# STM32.net
KiCad netlist of a schematic drawn in Altium Designer
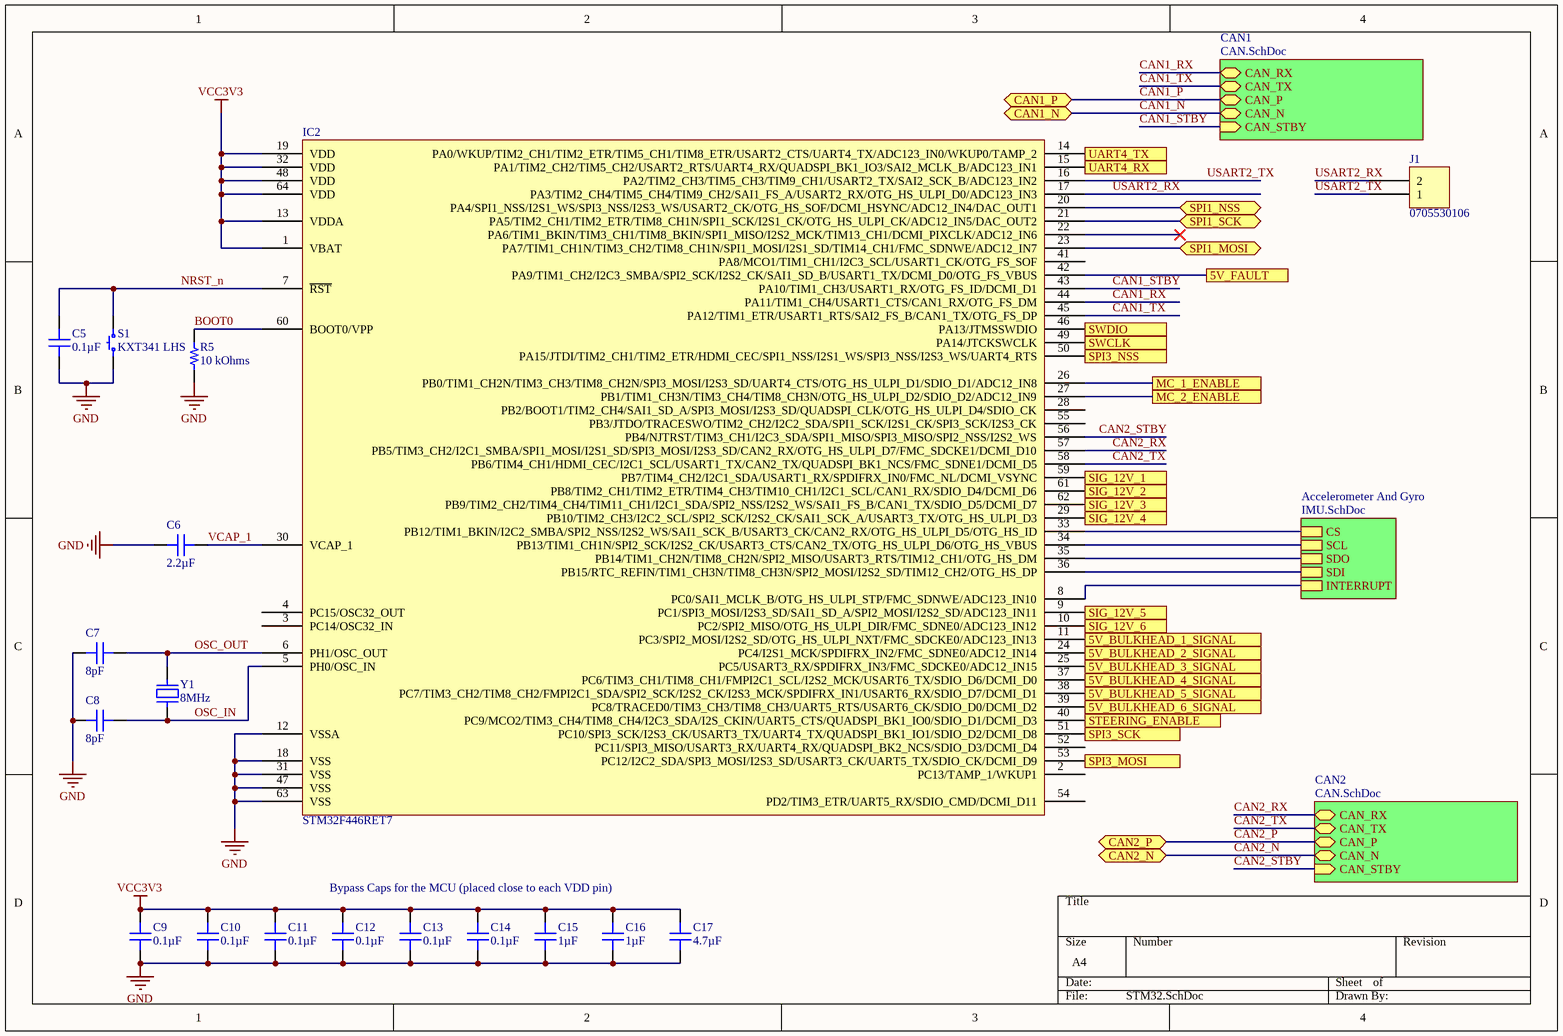
[diagram p0: STM32.SchDoc]

(export (version "E")
  (design (tool "Eeschema 10.0.6"))
  (components
    (comp (ref "C5")
      (value "0.1µF")
      (footprint "CAP 0402_1005")
      (description "CAP CER 0402 0.1UF 16V X7R 10%")
      (fields (field (name "PART NUMBER") "C0402C104K4RECAUTO") (field (name "MANUFACTURER") "KEMET"))
      (libsource (lib "CAL") (part "Capacitor"))
    )
    (comp (ref "C6")
      (value "2.2µF")
      (footprint "CAP 0402_1005")
      (description "CAP CER 2.2UF 16V X5R 0402")
      (fields
        (field (name "PART NUMBER") "CL05A225KO5NQNC")
        (field (name "MANUFACTURER") "Samsung Electro-Mechanics")
      )
      (libsource (lib "CAL") (part "Capacitor"))
    )
    (comp (ref "C7")
      (value "8pF")
      (footprint "CAP 0402_1005")
      (description "CAP CER 8PF 50V NP0 0402")
      (fields
        (field (name "PART NUMBER") "C1005NP01H080D050BA")
        (field (name "MANUFACTURER") "TDK Corporation")
      )
      (libsource (lib "Celestial") (part "Capacitor"))
    )
    (comp (ref "C8")
      (value "8pF")
      (footprint "CAP 0402_1005")
      (description "CAP CER 8PF 50V NP0 0402")
      (fields
        (field (name "PART NUMBER") "C1005NP01H080D050BA")
        (field (name "MANUFACTURER") "TDK Corporation")
      )
      (libsource (lib "Celestial") (part "Capacitor"))
    )
    (comp (ref "C9")
      (value "0.1µF")
      (footprint "CAP 0402_1005")
      (description "CAP CER 0402 0.1UF 16V X7R 10%")
      (fields (field (name "PART NUMBER") "C0402C104K4RECAUTO") (field (name "MANUFACTURER") "KEMET"))
      (libsource (lib "CAL") (part "Capacitor"))
    )
    (comp (ref "C10")
      (value "0.1µF")
      (footprint "CAP 0402_1005")
      (description "CAP CER 0402 0.1UF 16V X7R 10%")
      (fields (field (name "PART NUMBER") "C0402C104K4RECAUTO") (field (name "MANUFACTURER") "KEMET"))
      (libsource (lib "CAL") (part "Capacitor"))
    )
    (comp (ref "C11")
      (value "0.1µF")
      (footprint "CAP 0402_1005")
      (description "CAP CER 0402 0.1UF 16V X7R 10%")
      (fields (field (name "PART NUMBER") "C0402C104K4RECAUTO") (field (name "MANUFACTURER") "KEMET"))
      (libsource (lib "CAL") (part "Capacitor"))
    )
    (comp (ref "C12")
      (value "0.1µF")
      (footprint "CAP 0402_1005")
      (description "CAP CER 0402 0.1UF 16V X7R 10%")
      (fields (field (name "PART NUMBER") "C0402C104K4RECAUTO") (field (name "MANUFACTURER") "KEMET"))
      (libsource (lib "CAL") (part "Capacitor"))
    )
    (comp (ref "C13")
      (value "0.1µF")
      (footprint "CAP 0402_1005")
      (description "CAP CER 0402 0.1UF 16V X7R 10%")
      (fields (field (name "PART NUMBER") "C0402C104K4RECAUTO") (field (name "MANUFACTURER") "KEMET"))
      (libsource (lib "CAL") (part "Capacitor"))
    )
    (comp (ref "C14")
      (value "0.1µF")
      (footprint "CAP 0402_1005")
      (description "CAP CER 0402 0.1UF 16V X7R 10%")
      (fields (field (name "PART NUMBER") "C0402C104K4RECAUTO") (field (name "MANUFACTURER") "KEMET"))
      (libsource (lib "CAL") (part "Capacitor"))
    )
    (comp (ref "C15")
      (value "1µF")
      (footprint "CAP 0402_1005")
      (description "CAP CER 1UF 10V X5R 0402")
      (fields
        (field (name "PART NUMBER") "CGB2A1X5R1A105K033BC")
        (field (name "MANUFACTURER") "TDK Corporation")
      )
      (libsource (lib "CAL") (part "Capacitor"))
    )
    (comp (ref "C16")
      (value "1µF")
      (footprint "CAP 0402_1005")
      (description "CAP CER 1UF 10V X5R 0402")
      (fields
        (field (name "PART NUMBER") "CGB2A1X5R1A105K033BC")
        (field (name "MANUFACTURER") "TDK Corporation")
      )
      (libsource (lib "CAL") (part "Capacitor"))
    )
    (comp (ref "C17")
      (value "4.7µF")
      (footprint "CAP 0402_1005")
      (description "CAP CER 4.7UF 10V X5R 0402")
      (fields
        (field (name "PART NUMBER") "C1005X5R1A475K050BC")
        (field (name "MANUFACTURER") "TDK Corporation")
      )
      (libsource (lib "CAL") (part "Capacitor"))
    )
    (comp (ref "IC2")
      (value "STM32F446RET7")
      (footprint "ST LQFP-64 10X10MM")
      (description "IC MCU 32BIT 512KB FLASH 64LQFP")
      (fields (field (name "MANUFACTURER") "STMicroelectronics"))
      (libsource (lib "Celestial") (part "ST STM32F446 64PIN"))
    )
    (comp (ref "J1")
      (value "0705530106")
      (footprint "MOLEX SDA-70553-2PIN")
      (description "CONN HEADER R/A 2POS 2.54MM")
      (fields (field (name "MANUFACTURER") "Molex"))
      (libsource (lib "Celestial") (part "2 Pin"))
    )
    (comp (ref "R5")
      (value "10 kOhms")
      (footprint "RES 0402_1005")
      (description "RES SMD 10K OHM 0.5% 1/16W 0402")
      (fields (field (name "PART NUMBER") "CRCW040210K0DHEDP") (field (name "MANUFACTURER") "Vishay Dale"))
      (libsource (lib "CAL") (part "Resistor"))
    )
    (comp (ref "S1")
      (value "KXT341 LHS")
      (footprint "C&K KXT3")
      (description "SWITCH TACTILE SPST-NO 0.02A 15V")
      (fields (field (name "MANUFACTURER") "C&K"))
      (libsource (lib "Celestial") (part "SPST-NO 2 PIN"))
    )
    (comp (ref "Y1")
      (value "8MHz")
      (footprint "NDK NX3225GD")
      (description "CRYSTAL 8.0000MHZ 8PF SMD")
      (fields
        (field (name "PART NUMBER") "NX3225GD-8MHZ-STD-CRA-3")
        (field (name "MANUFACTURER") "NDK America, Inc.")
      )
      (libsource (lib "Celestial") (part "NDK NX3225GD"))
    )
  )
  (nets
    (net (code "1") (name "/5V_BULKHEAD_1_SIGNAL") (class "Default")
      (node (ref "IC2") (pin "11") (pinfunction "PC3/SPI2_MOSI/I2S2_SD/OTG_HS_ULPI_NXT/FMC_SDCKE0/ADC123_IN13_11") (pintype "passive"))
    )
    (net (code "2") (name "/5V_BULKHEAD_2_SIGNAL") (class "Default")
      (node (ref "IC2") (pin "24") (pinfunction "PC4/I2S1_MCK/SPDIFRX_IN2/FMC_SDNE0/ADC12_IN14_24") (pintype "passive"))
    )
    (net (code "3") (name "/5V_BULKHEAD_3_SIGNAL") (class "Default")
      (node (ref "IC2") (pin "25") (pinfunction "PC5/USART3_RX/SPDIFRX_IN3/FMC_SDCKE0/ADC12_IN15_25") (pintype "passive"))
    )
    (net (code "4") (name "/5V_BULKHEAD_4_SIGNAL") (class "Default")
      (node (ref "IC2") (pin "37") (pinfunction "PC6/TIM3_CH1/TIM8_CH1/FMPI2C1_SCL/I2S2_MCK/USART6_TX/SDIO_D6/DCMI_D0_37") (pintype "passive"))
    )
    (net (code "5") (name "/5V_BULKHEAD_5_SIGNAL") (class "Default")
      (node (ref "IC2") (pin "38") (pinfunction "PC7/TIM3_CH2/TIM8_CH2/FMPI2C1_SDA/SPI2_SCK/I2S2_CK/I2S3_MCK/SPDIFRX_IN1/USART6_RX/SDIO_D7/DCMI_D1_38") (pintype "passive"))
    )
    (net (code "6") (name "/5V_BULKHEAD_6_SIGNAL") (class "Default")
      (node (ref "IC2") (pin "39") (pinfunction "PC8/TRACED0/TIM3_CH3/TIM8_CH3/UART5_RTS/USART6_CK/SDIO_D0/DCMI_D2_39") (pintype "passive"))
    )
    (net (code "7") (name "/5V_FAULT") (class "Default")
      (node (ref "IC2") (pin "42") (pinfunction "PA9/TIM1_CH2/I2C3_SMBA/SPI2_SCK/I2S2_CK/SAI1_SD_B/USART1_TX/DCMI_D0/OTG_FS_VBUS_42") (pintype "passive"))
    )
    (net (code "8") (name "/BOOT0") (class "Default")
      (node (ref "IC2") (pin "60") (pinfunction "BOOT0/VPP_60") (pintype "passive"))
      (node (ref "R5") (pin "2") (pinfunction "2_2") (pintype "passive"))
    )
    (net (code "11") (name "/CAN1_RX") (class "Default")
      (node (ref "IC2") (pin "44") (pinfunction "PA11/TIM1_CH4/USART1_CTS/CAN1_RX/OTG_FS_DM_44") (pintype "passive"))
    )
    (net (code "12") (name "/CAN1_STBY") (class "Default")
      (node (ref "IC2") (pin "43") (pinfunction "PA10/TIM1_CH3/USART1_RX/OTG_FS_ID/DCMI_D1_43") (pintype "passive"))
    )
    (net (code "13") (name "/CAN1_TX") (class "Default")
      (node (ref "IC2") (pin "45") (pinfunction "PA12/TIM1_ETR/USART1_RTS/SAI2_FS_B/CAN1_TX/OTG_FS_DP_45") (pintype "passive"))
    )
    (net (code "16") (name "/CAN2_RX") (class "Default")
      (node (ref "IC2") (pin "57") (pinfunction "PB5/TIM3_CH2/I2C1_SMBA/SPI1_MOSI/I2S1_SD/SPI3_MOSI/I2S3_SD/CAN2_RX/OTG_HS_ULPI_D7/FMC_SDCKE1/DCMI_D10_57") (pintype "passive"))
    )
    (net (code "17") (name "/CAN2_STBY") (class "Default")
      (node (ref "IC2") (pin "56") (pinfunction "PB4/NJTRST/TIM3_CH1/I2C3_SDA/SPI1_MISO/SPI3_MISO/SPI2_NSS/I2S2_WS_56") (pintype "passive"))
    )
    (net (code "18") (name "/CAN2_TX") (class "Default")
      (node (ref "IC2") (pin "58") (pinfunction "PB6/TIM4_CH1/HDMI_CEC/I2C1_SCL/USART1_TX/CAN2_TX/QUADSPI_BK1_NCS/FMC_SDNE1/DCMI_D5_58") (pintype "passive"))
    )
    (net (code "19") (name "/CS") (class "Default")
      (node (ref "IC2") (pin "33") (pinfunction "PB12/TIM1_BKIN/I2C2_SMBA/SPI2_NSS/I2S2_WS/SAI1_SCK_B/USART3_CK/CAN2_RX/OTG_HS_ULPI_D5/OTG_HS_ID_33") (pintype "passive"))
    )
    (net (code "20") (name "/INTERRUPT") (class "Default")
      (node (ref "IC2") (pin "8") (pinfunction "PC0/SAI1_MCLK_B/OTG_HS_ULPI_STP/FMC_SDNWE/ADC123_IN10_8") (pintype "passive"))
    )
    (net (code "21") (name "/MC_1_ENABLE") (class "Default")
      (node (ref "IC2") (pin "26") (pinfunction "PB0/TIM1_CH2N/TIM3_CH3/TIM8_CH2N/SPI3_MOSI/I2S3_SD/UART4_CTS/OTG_HS_ULPI_D1/SDIO_D1/ADC12_IN8_26") (pintype "passive"))
    )
    (net (code "22") (name "/MC_2_ENABLE") (class "Default")
      (node (ref "IC2") (pin "27") (pinfunction "PB1/TIM1_CH3N/TIM3_CH4/TIM8_CH3N/OTG_HS_ULPI_D2/SDIO_D2/ADC12_IN9_27") (pintype "passive"))
    )
    (net (code "23") (name "/NRST_n") (class "Default")
      (node (ref "C5") (pin "2") (pinfunction "2_2") (pintype "passive"))
      (node (ref "IC2") (pin "7") (pinfunction "~{RST}_7") (pintype "passive"))
      (node (ref "S1") (pin "2") (pinfunction "2_2") (pintype "passive"))
    )
    (net (code "24") (name "/OSC_IN") (class "Default")
      (node (ref "C8") (pin "2") (pinfunction "2_2") (pintype "passive"))
      (node (ref "IC2") (pin "5") (pinfunction "PH0/OSC_IN_5") (pintype "passive"))
      (node (ref "Y1") (pin "1") (pinfunction "1_1") (pintype "passive"))
    )
    (net (code "25") (name "/OSC_OUT") (class "Default")
      (node (ref "C7") (pin "2") (pinfunction "2_2") (pintype "passive"))
      (node (ref "IC2") (pin "6") (pinfunction "PH1/OSC_OUT_6") (pintype "passive"))
      (node (ref "Y1") (pin "2") (pinfunction "2_2") (pintype "passive"))
    )
    (net (code "26") (name "/SCL") (class "Default")
      (node (ref "IC2") (pin "34") (pinfunction "PB13/TIM1_CH1N/SPI2_SCK/I2S2_CK/USART3_CTS/CAN2_TX/OTG_HS_ULPI_D6/OTG_HS_VBUS_34") (pintype "passive"))
    )
    (net (code "27") (name "/SDI") (class "Default")
      (node (ref "IC2") (pin "36") (pinfunction "PB15/RTC_REFIN/TIM1_CH3N/TIM8_CH3N/SPI2_MOSI/I2S2_SD/TIM12_CH2/OTG_HS_DP_36") (pintype "passive"))
    )
    (net (code "28") (name "/SDO") (class "Default")
      (node (ref "IC2") (pin "35") (pinfunction "PB14/TIM1_CH2N/TIM8_CH2N/SPI2_MISO/USART3_RTS/TIM12_CH1/OTG_HS_DM_35") (pintype "passive"))
    )
    (net (code "29") (name "/SIG_12V_1") (class "Default")
      (node (ref "IC2") (pin "59") (pinfunction "PB7/TIM4_CH2/I2C1_SDA/USART1_RX/SPDIFRX_IN0/FMC_NL/DCMI_VSYNC_59") (pintype "passive"))
    )
    (net (code "30") (name "/SIG_12V_2") (class "Default")
      (node (ref "IC2") (pin "61") (pinfunction "PB8/TIM2_CH1/TIM2_ETR/TIM4_CH3/TIM10_CH1/I2C1_SCL/CAN1_RX/SDIO_D4/DCMI_D6_61") (pintype "passive"))
    )
    (net (code "31") (name "/SIG_12V_3") (class "Default")
      (node (ref "IC2") (pin "62") (pinfunction "PB9/TIM2_CH2/TIM4_CH4/TIM11_CH1/I2C1_SDA/SPI2_NSS/I2S2_WS/SAI1_FS_B/CAN1_TX/SDIO_D5/DCMI_D7_62") (pintype "passive"))
    )
    (net (code "32") (name "/SIG_12V_4") (class "Default")
      (node (ref "IC2") (pin "29") (pinfunction "PB10/TIM2_CH3/I2C2_SCL/SPI2_SCK/I2S2_CK/SAI1_SCK_A/USART3_TX/OTG_HS_ULPI_D3_29") (pintype "passive"))
    )
    (net (code "33") (name "/SIG_12V_5") (class "Default")
      (node (ref "IC2") (pin "9") (pinfunction "PC1/SPI3_MOSI/I2S3_SD/SAI1_SD_A/SPI2_MOSI/I2S2_SD/ADC123_IN11_9") (pintype "passive"))
    )
    (net (code "34") (name "/SIG_12V_6") (class "Default")
      (node (ref "IC2") (pin "10") (pinfunction "PC2/SPI2_MISO/OTG_HS_ULPI_DIR/FMC_SDNE0/ADC123_IN12_10") (pintype "passive"))
    )
    (net (code "35") (name "/SPI1_MOSI") (class "Default")
      (node (ref "IC2") (pin "23") (pinfunction "PA7/TIM1_CH1N/TIM3_CH2/TIM8_CH1N/SPI1_MOSI/I2S1_SD/TIM14_CH1/FMC_SDNWE/ADC12_IN7_23") (pintype "passive"))
    )
    (net (code "36") (name "/SPI1_NSS") (class "Default")
      (node (ref "IC2") (pin "20") (pinfunction "PA4/SPI1_NSS/I2S1_WS/SPI3_NSS/I2S3_WS/USART2_CK/OTG_HS_SOF/DCMI_HSYNC/ADC12_IN4/DAC_OUT1_20") (pintype "passive"))
    )
    (net (code "37") (name "/SPI1_SCK") (class "Default")
      (node (ref "IC2") (pin "21") (pinfunction "PA5/TIM2_CH1/TIM2_ETR/TIM8_CH1N/SPI1_SCK/I2S1_CK/OTG_HS_ULPI_CK/ADC12_IN5/DAC_OUT2_21") (pintype "passive"))
    )
    (net (code "38") (name "/SPI3_MOSI") (class "Default")
      (node (ref "IC2") (pin "53") (pinfunction "PC12/I2C2_SDA/SPI3_MOSI/I2S3_SD/USART3_CK/UART5_TX/SDIO_CK/DCMI_D9_53") (pintype "passive"))
    )
    (net (code "39") (name "/SPI3_NSS") (class "Default")
      (node (ref "IC2") (pin "50") (pinfunction "PA15/JTDI/TIM2_CH1/TIM2_ETR/HDMI_CEC/SPI1_NSS/I2S1_WS/SPI3_NSS/I2S3_WS/UART4_RTS_50") (pintype "passive"))
    )
    (net (code "40") (name "/SPI3_SCK") (class "Default")
      (node (ref "IC2") (pin "51") (pinfunction "PC10/SPI3_SCK/I2S3_CK/USART3_TX/UART4_TX/QUADSPI_BK1_IO1/SDIO_D2/DCMI_D8_51") (pintype "passive"))
    )
    (net (code "41") (name "/STEERING_ENABLE") (class "Default")
      (node (ref "IC2") (pin "40") (pinfunction "PC9/MCO2/TIM3_CH4/TIM8_CH4/I2C3_SDA/I2S_CKIN/UART5_CTS/QUADSPI_BK1_IO0/SDIO_D1/DCMI_D3_40") (pintype "passive"))
    )
    (net (code "42") (name "/SWCLK") (class "Default")
      (node (ref "IC2") (pin "49") (pinfunction "PA14/JTCKSWCLK_49") (pintype "passive"))
    )
    (net (code "43") (name "/SWDIO") (class "Default")
      (node (ref "IC2") (pin "46") (pinfunction "PA13/JTMSSWDIO_46") (pintype "passive"))
    )
    (net (code "44") (name "/UART4_RX") (class "Default")
      (node (ref "IC2") (pin "15") (pinfunction "PA1/TIM2_CH2/TIM5_CH2/USART2_RTS/UART4_RX/QUADSPI_BK1_IO3/SAI2_MCLK_B/ADC123_IN1_15") (pintype "passive"))
    )
    (net (code "45") (name "/UART4_TX") (class "Default")
      (node (ref "IC2") (pin "14") (pinfunction "PA0/WKUP/TIM2_CH1/TIM2_ETR/TIM5_CH1/TIM8_ETR/USART2_CTS/UART4_TX/ADC123_IN0/WKUP0/TAMP_2_14") (pintype "passive"))
    )
    (net (code "46") (name "/USART2_RX") (class "Default")
      (node (ref "IC2") (pin "17") (pinfunction "PA3/TIM2_CH4/TIM5_CH4/TIM9_CH2/SAI1_FS_A/USART2_RX/OTG_HS_ULPI_D0/ADC123_IN3_17") (pintype "passive"))
      (node (ref "J1") (pin "2") (pinfunction "2_2") (pintype "passive"))
    )
    (net (code "47") (name "/USART2_TX") (class "Default")
      (node (ref "IC2") (pin "16") (pinfunction "PA2/TIM2_CH3/TIM5_CH3/TIM9_CH1/USART2_TX/SAI2_SCK_B/ADC123_IN2_16") (pintype "passive"))
      (node (ref "J1") (pin "1") (pinfunction "1_1") (pintype "passive"))
    )
    (net (code "48") (name "/VCAP_1") (class "Default")
      (node (ref "C6") (pin "1") (pinfunction "1_1") (pintype "passive"))
      (node (ref "IC2") (pin "30") (pinfunction "VCAP_1_30") (pintype "passive"))
    )
    (net (code "49") (name "GND") (class "Default")
      (node (ref "C10") (pin "1") (pinfunction "1_1") (pintype "passive"))
      (node (ref "C11") (pin "1") (pinfunction "1_1") (pintype "passive"))
      (node (ref "C12") (pin "1") (pinfunction "1_1") (pintype "passive"))
      (node (ref "C13") (pin "1") (pinfunction "1_1") (pintype "passive"))
      (node (ref "C14") (pin "1") (pinfunction "1_1") (pintype "passive"))
      (node (ref "C15") (pin "1") (pinfunction "1_1") (pintype "passive"))
      (node (ref "C16") (pin "1") (pinfunction "1_1") (pintype "passive"))
      (node (ref "C17") (pin "1") (pinfunction "1_1") (pintype "passive"))
      (node (ref "C5") (pin "1") (pinfunction "1_1") (pintype "passive"))
      (node (ref "C6") (pin "2") (pinfunction "2_2") (pintype "passive"))
      (node (ref "C7") (pin "1") (pinfunction "1_1") (pintype "passive"))
      (node (ref "C8") (pin "1") (pinfunction "1_1") (pintype "passive"))
      (node (ref "C9") (pin "1") (pinfunction "1_1") (pintype "passive"))
      (node (ref "IC2") (pin "12") (pinfunction "VSSA_12") (pintype "passive"))
      (node (ref "IC2") (pin "18") (pinfunction "VSS_18") (pintype "passive"))
      (node (ref "IC2") (pin "31") (pinfunction "VSS_31") (pintype "passive"))
      (node (ref "IC2") (pin "47") (pinfunction "VSS_47") (pintype "passive"))
      (node (ref "IC2") (pin "63") (pinfunction "VSS_63") (pintype "passive"))
      (node (ref "R5") (pin "1") (pinfunction "1_1") (pintype "passive"))
      (node (ref "S1") (pin "1") (pinfunction "1_1") (pintype "passive"))
    )
    (net (code "50") (name "VCC3V3") (class "Default")
      (node (ref "C10") (pin "2") (pinfunction "2_2") (pintype "passive"))
      (node (ref "C11") (pin "2") (pinfunction "2_2") (pintype "passive"))
      (node (ref "C12") (pin "2") (pinfunction "2_2") (pintype "passive"))
      (node (ref "C13") (pin "2") (pinfunction "2_2") (pintype "passive"))
      (node (ref "C14") (pin "2") (pinfunction "2_2") (pintype "passive"))
      (node (ref "C15") (pin "2") (pinfunction "2_2") (pintype "passive"))
      (node (ref "C16") (pin "2") (pinfunction "2_2") (pintype "passive"))
      (node (ref "C17") (pin "2") (pinfunction "2_2") (pintype "passive"))
      (node (ref "C9") (pin "2") (pinfunction "2_2") (pintype "passive"))
      (node (ref "IC2") (pin "1") (pinfunction "VBAT_1") (pintype "passive"))
      (node (ref "IC2") (pin "13") (pinfunction "VDDA_13") (pintype "passive"))
      (node (ref "IC2") (pin "19") (pinfunction "VDD_19") (pintype "passive"))
      (node (ref "IC2") (pin "32") (pinfunction "VDD_32") (pintype "passive"))
      (node (ref "IC2") (pin "48") (pinfunction "VDD_48") (pintype "passive"))
      (node (ref "IC2") (pin "64") (pinfunction "VDD_64") (pintype "passive"))
    )
    (net (code "51") (name "unconnected-(IC2-PA6{slash}TIM1_BKIN{slash}TIM3_CH1{slash}TIM8_BKIN{slash}SPI1_MISO{slash}I2S2_MCK{slash}TIM13_CH1{slash}DCMI_PIXCLK{slash}ADC12_IN6-Pad22)") (class "Default")
      (node (ref "IC2") (pin "22") (pinfunction "PA6/TIM1_BKIN/TIM3_CH1/TIM8_BKIN/SPI1_MISO/I2S2_MCK/TIM13_CH1/DCMI_PIXCLK/ADC12_IN6_22") (pintype "passive+no_connect"))
    )
    (net (code "52") (name "unconnected-(IC2-PA8{slash}MCO1{slash}TIM1_CH1{slash}I2C3_SCL{slash}USART1_CK{slash}OTG_FS_SOF-Pad41)") (class "Default")
      (node (ref "IC2") (pin "41") (pinfunction "PA8/MCO1/TIM1_CH1/I2C3_SCL/USART1_CK/OTG_FS_SOF_41") (pintype "passive"))
    )
    (net (code "53") (name "unconnected-(IC2-PB2{slash}BOOT1{slash}TIM2_CH4{slash}SAI1_SD_A{slash}SPI3_MOSI{slash}I2S3_SD{slash}QUADSPI_CLK{slash}OTG_HS_ULPI_D4{slash}SDIO_CK-Pad28)") (class "Default")
      (node (ref "IC2") (pin "28") (pinfunction "PB2/BOOT1/TIM2_CH4/SAI1_SD_A/SPI3_MOSI/I2S3_SD/QUADSPI_CLK/OTG_HS_ULPI_D4/SDIO_CK_28") (pintype "passive"))
    )
    (net (code "54") (name "unconnected-(IC2-PB3{slash}JTDO{slash}TRACESWO{slash}TIM2_CH2{slash}I2C2_SDA{slash}SPI1_SCK{slash}I2S1_CK{slash}SPI3_SCK{slash}I2S3_CK-Pad55)") (class "Default")
      (node (ref "IC2") (pin "55") (pinfunction "PB3/JTDO/TRACESWO/TIM2_CH2/I2C2_SDA/SPI1_SCK/I2S1_CK/SPI3_SCK/I2S3_CK_55") (pintype "passive"))
    )
    (net (code "55") (name "unconnected-(IC2-PC11{slash}SPI3_MISO{slash}USART3_RX{slash}UART4_RX{slash}QUADSPI_BK2_NCS{slash}SDIO_D3{slash}DCMI_D4-Pad52)") (class "Default")
      (node (ref "IC2") (pin "52") (pinfunction "PC11/SPI3_MISO/USART3_RX/UART4_RX/QUADSPI_BK2_NCS/SDIO_D3/DCMI_D4_52") (pintype "passive"))
    )
    (net (code "56") (name "unconnected-(IC2-PC13{slash}TAMP_1{slash}WKUP1-Pad2)") (class "Default")
      (node (ref "IC2") (pin "2") (pinfunction "PC13/TAMP_1/WKUP1_2") (pintype "passive"))
    )
    (net (code "57") (name "unconnected-(IC2-PC14{slash}OSC32_IN-Pad3)") (class "Default")
      (node (ref "IC2") (pin "3") (pinfunction "PC14/OSC32_IN_3") (pintype "passive"))
    )
    (net (code "58") (name "unconnected-(IC2-PC15{slash}OSC32_OUT-Pad4)") (class "Default")
      (node (ref "IC2") (pin "4") (pinfunction "PC15/OSC32_OUT_4") (pintype "passive"))
    )
    (net (code "59") (name "unconnected-(IC2-PD2{slash}TIM3_ETR{slash}UART5_RX{slash}SDIO_CMD{slash}DCMI_D11-Pad54)") (class "Default")
      (node (ref "IC2") (pin "54") (pinfunction "PD2/TIM3_ETR/UART5_RX/SDIO_CMD/DCMI_D11_54") (pintype "passive"))
    )
  )
)
